# 12_USB_3.net
KiCad netlist of a schematic drawn in Altium Designer
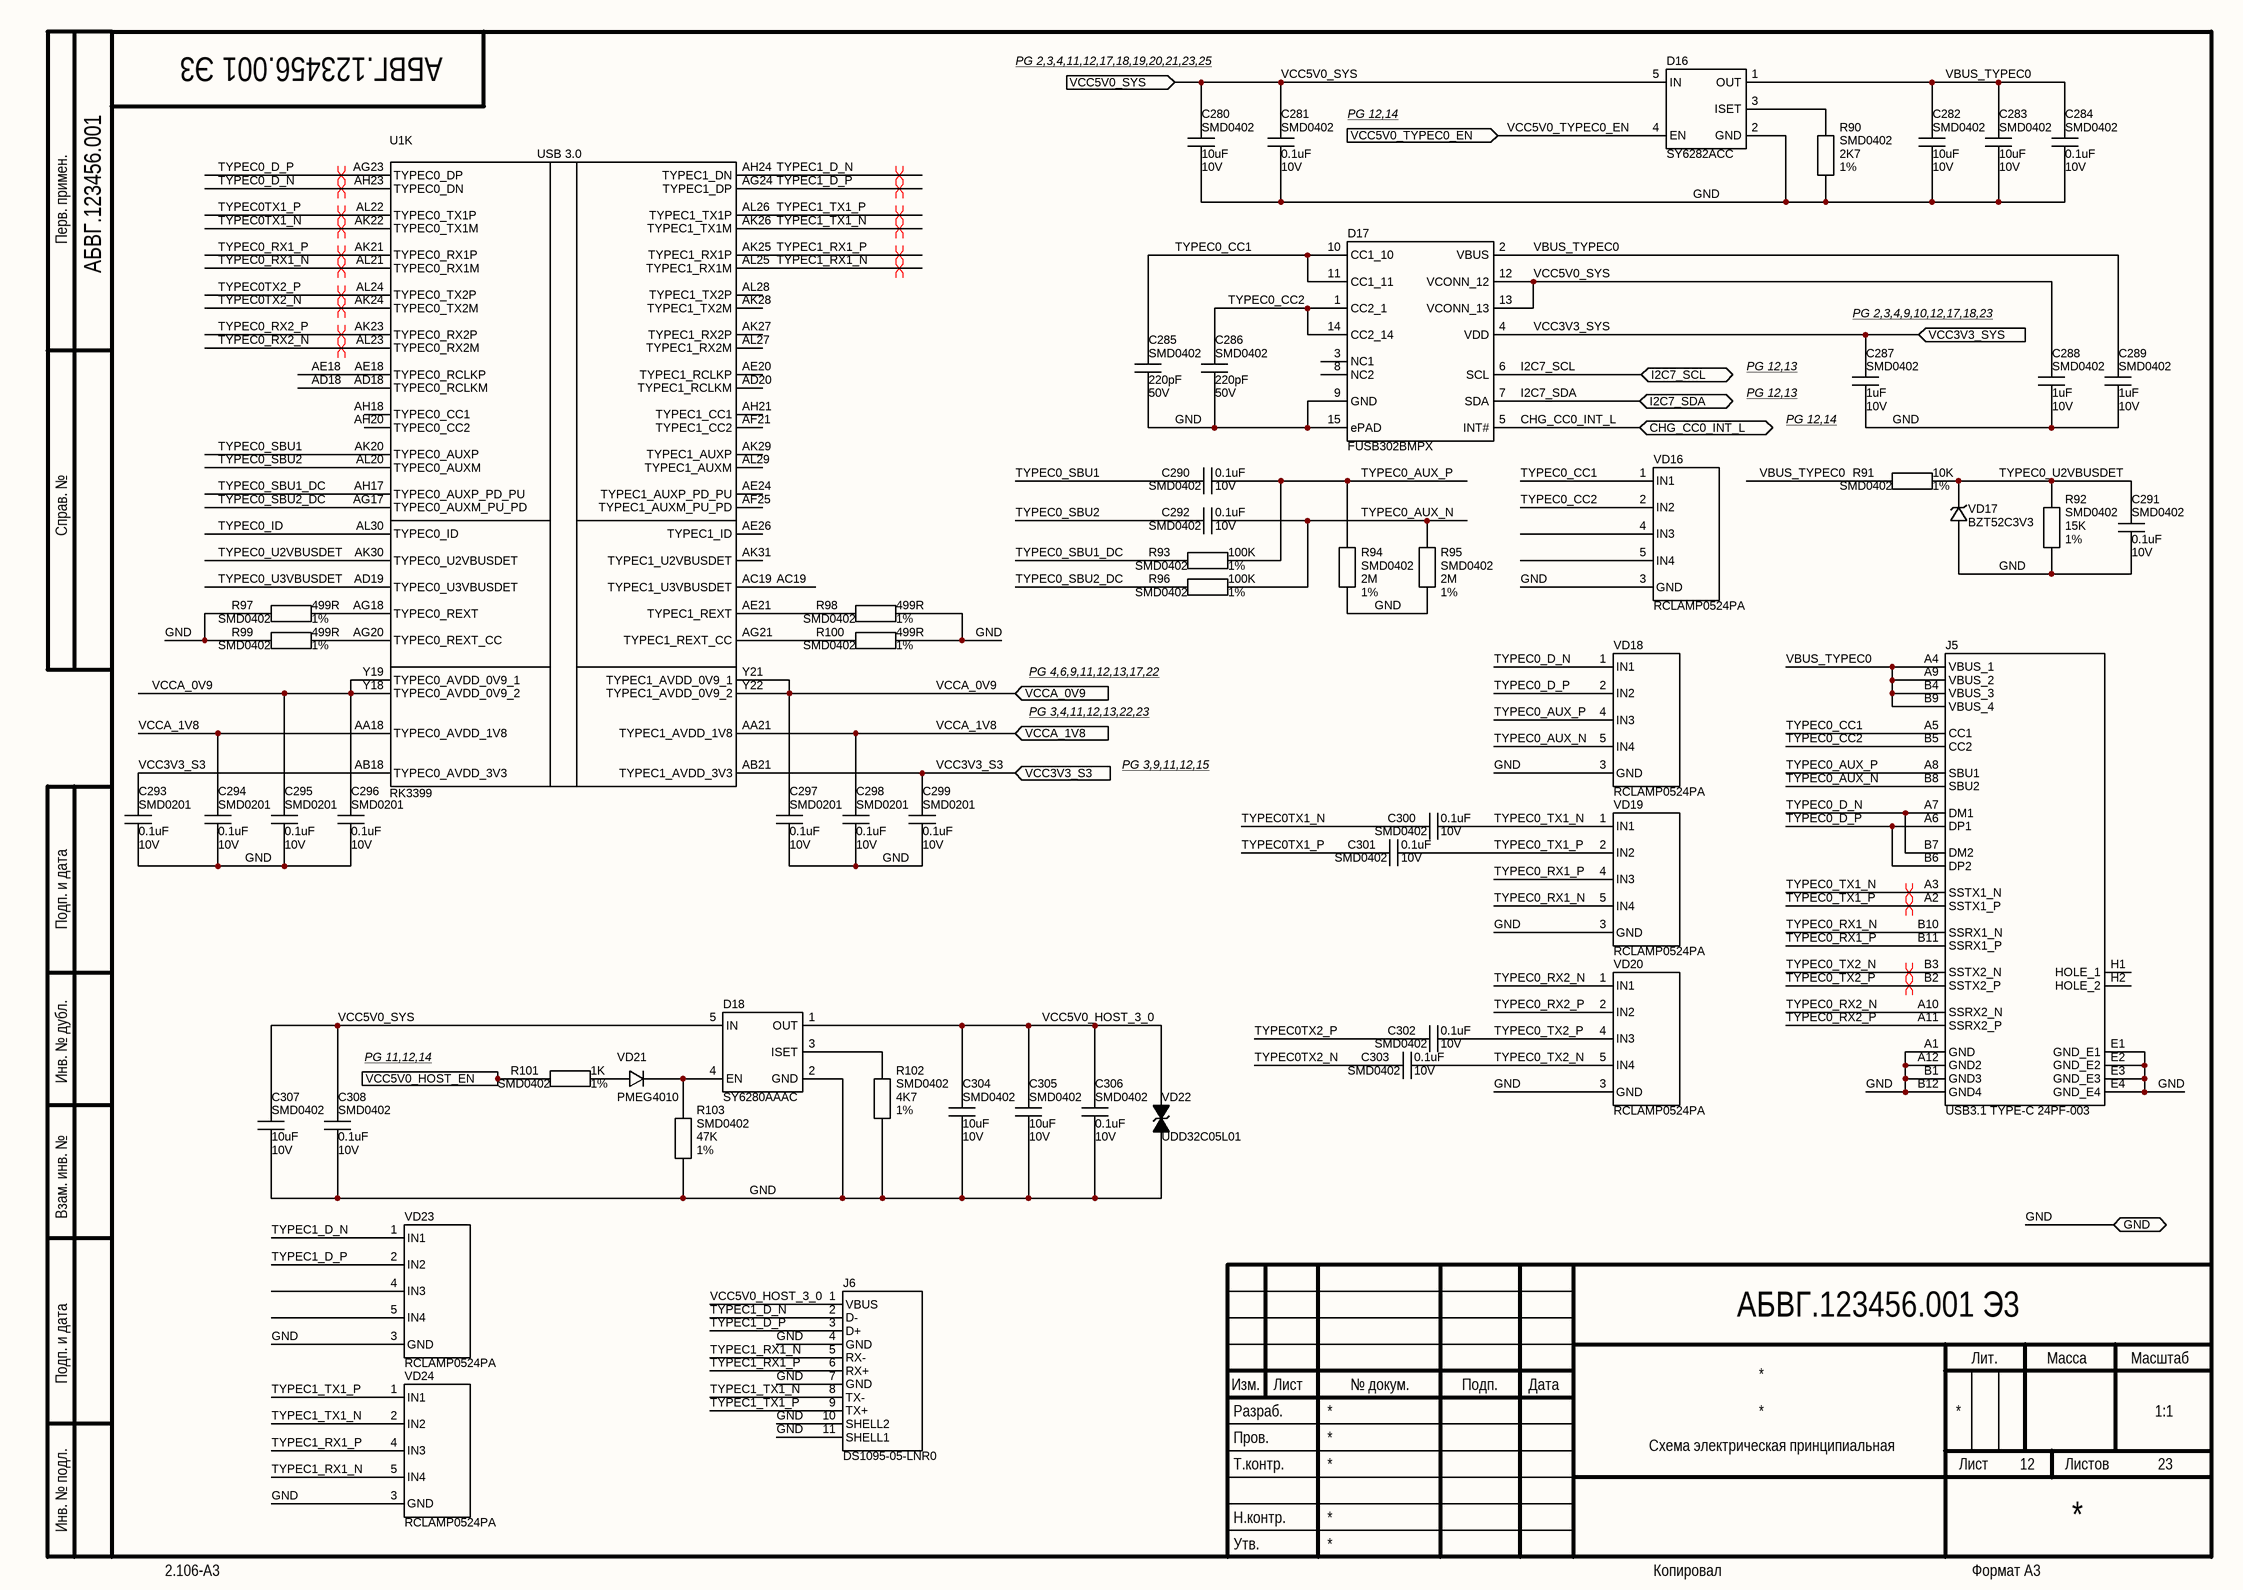
[diagram p0: 12 USB_3.SchDoc]

(export (version "E")
  (design (tool "Eeschema 10.0.6"))
  (components
    (comp (ref "C280")
      (value "10uF")
      (footprint "Didur_PcbLib_1:CAP_SMD_0402")
      (fields
        (field (name "PACKAGE") "SMD0402")
        (field (name "PARTNUMBER") "CC0402MRX5R6BB106")
        (field (name "VOLTAGE") "10V")
      )
      (libsource (lib "Didur_SchLib_1") (part "Ceramic_Cap"))
    )
    (comp (ref "C281")
      (value "0.1uF")
      (footprint "Didur_PcbLib_1:CAP_SMD_0402")
      (fields
        (field (name "PACKAGE") "SMD0402")
        (field (name "PARTNUMBER") "CC0402KRX5R6BB104")
        (field (name "VOLTAGE") "10V")
      )
      (libsource (lib "Didur_SchLib_1") (part "Ceramic_Cap"))
    )
    (comp (ref "C282")
      (value "10uF")
      (footprint "Didur_PcbLib_1:CAP_SMD_0402")
      (fields
        (field (name "PACKAGE") "SMD0402")
        (field (name "PARTNUMBER") "CC0402MRX5R6BB106")
        (field (name "VOLTAGE") "10V")
      )
      (libsource (lib "Didur_SchLib_1") (part "Ceramic_Cap"))
    )
    (comp (ref "C283")
      (value "10uF")
      (footprint "Didur_PcbLib_1:CAP_SMD_0402")
      (fields
        (field (name "PACKAGE") "SMD0402")
        (field (name "PARTNUMBER") "CC0402MRX5R6BB106")
        (field (name "VOLTAGE") "10V")
      )
      (libsource (lib "Didur_SchLib_1") (part "Ceramic_Cap"))
    )
    (comp (ref "C284")
      (value "0.1uF")
      (footprint "Didur_PcbLib_1:CAP_SMD_0402")
      (fields
        (field (name "PACKAGE") "SMD0402")
        (field (name "PARTNUMBER") "CC0402KRX5R6BB104")
        (field (name "VOLTAGE") "10V")
      )
      (libsource (lib "Didur_SchLib_1") (part "Ceramic_Cap"))
    )
    (comp (ref "C285")
      (value "220pF")
      (footprint "Didur_PcbLib_1:CAP_SMD_0402")
      (fields
        (field (name "PACKAGE") "SMD0402")
        (field (name "PARTNUMBER") "CC0402JRNPO9BN221")
        (field (name "VOLTAGE") "50V")
      )
      (libsource (lib "Didur_SchLib_1") (part "Ceramic_Cap"))
    )
    (comp (ref "C286")
      (value "220pF")
      (footprint "Didur_PcbLib_1:CAP_SMD_0402")
      (fields
        (field (name "PACKAGE") "SMD0402")
        (field (name "PARTNUMBER") "CC0402JRNPO9BN221")
        (field (name "VOLTAGE") "50V")
      )
      (libsource (lib "Didur_SchLib_1") (part "Ceramic_Cap"))
    )
    (comp (ref "C287")
      (value "1uF")
      (footprint "Didur_PcbLib_1:CAP_SMD_0402")
      (fields
        (field (name "PACKAGE") "SMD0402")
        (field (name "PARTNUMBER") "CC0402KRX5R6BB105")
        (field (name "VOLTAGE") "10V")
      )
      (libsource (lib "Didur_SchLib_1") (part "Ceramic_Cap"))
    )
    (comp (ref "C288")
      (value "1uF")
      (footprint "Didur_PcbLib_1:CAP_SMD_0402")
      (fields
        (field (name "PACKAGE") "SMD0402")
        (field (name "PARTNUMBER") "CC0402KRX5R6BB105")
        (field (name "VOLTAGE") "10V")
      )
      (libsource (lib "Didur_SchLib_1") (part "Ceramic_Cap"))
    )
    (comp (ref "C289")
      (value "1uF")
      (footprint "Didur_PcbLib_1:CAP_SMD_0402")
      (fields
        (field (name "PACKAGE") "SMD0402")
        (field (name "PARTNUMBER") "CC0402KRX5R6BB105")
        (field (name "VOLTAGE") "10V")
      )
      (libsource (lib "Didur_SchLib_1") (part "Ceramic_Cap"))
    )
    (comp (ref "C290")
      (value "0.1uF")
      (footprint "Didur_PcbLib_1:CAP_SMD_0402")
      (fields
        (field (name "PACKAGE") "SMD0402")
        (field (name "PARTNUMBER") "CC0402KRX5R6BB104")
        (field (name "VOLTAGE") "10V")
      )
      (libsource (lib "Didur_SchLib_1") (part "Ceramic_Cap"))
    )
    (comp (ref "C291")
      (value "0.1uF")
      (footprint "Didur_PcbLib_1:CAP_SMD_0402")
      (fields
        (field (name "PACKAGE") "SMD0402")
        (field (name "PARTNUMBER") "CC0402KRX5R6BB104")
        (field (name "VOLTAGE") "10V")
      )
      (libsource (lib "Didur_SchLib_1") (part "Ceramic_Cap"))
    )
    (comp (ref "C292")
      (value "0.1uF")
      (footprint "Didur_PcbLib_1:CAP_SMD_0402")
      (fields
        (field (name "PACKAGE") "SMD0402")
        (field (name "PARTNUMBER") "CC0402KRX5R6BB104")
        (field (name "VOLTAGE") "10V")
      )
      (libsource (lib "Didur_SchLib_1") (part "Ceramic_Cap"))
    )
    (comp (ref "C293")
      (value "0.1uF")
      (footprint "Didur_PcbLib_1:CAP_SMD_0201")
      (fields
        (field (name "PACKAGE") "SMD0201")
        (field (name "PARTNUMBER") "CC0201KRX5R6BB104")
        (field (name "VOLTAGE") "10V")
      )
      (libsource (lib "Didur_SchLib_1") (part "Ceramic_Cap"))
    )
    (comp (ref "C294")
      (value "0.1uF")
      (footprint "Didur_PcbLib_1:CAP_SMD_0201")
      (fields
        (field (name "PACKAGE") "SMD0201")
        (field (name "PARTNUMBER") "CC0201KRX5R6BB104")
        (field (name "VOLTAGE") "10V")
      )
      (libsource (lib "Didur_SchLib_1") (part "Ceramic_Cap"))
    )
    (comp (ref "C295")
      (value "0.1uF")
      (footprint "Didur_PcbLib_1:CAP_SMD_0201")
      (fields
        (field (name "PACKAGE") "SMD0201")
        (field (name "PARTNUMBER") "CC0201KRX5R6BB104")
        (field (name "VOLTAGE") "10V")
      )
      (libsource (lib "Didur_SchLib_1") (part "Ceramic_Cap"))
    )
    (comp (ref "C296")
      (value "0.1uF")
      (footprint "Didur_PcbLib_1:CAP_SMD_0201")
      (fields
        (field (name "PACKAGE") "SMD0201")
        (field (name "PARTNUMBER") "CC0201KRX5R6BB104")
        (field (name "VOLTAGE") "10V")
      )
      (libsource (lib "Didur_SchLib_1") (part "Ceramic_Cap"))
    )
    (comp (ref "C297")
      (value "0.1uF")
      (footprint "Didur_PcbLib_1:CAP_SMD_0201")
      (fields
        (field (name "PACKAGE") "SMD0201")
        (field (name "PARTNUMBER") "CC0201KRX5R6BB104")
        (field (name "VOLTAGE") "10V")
      )
      (libsource (lib "Didur_SchLib_1") (part "Ceramic_Cap"))
    )
    (comp (ref "C298")
      (value "0.1uF")
      (footprint "Didur_PcbLib_1:CAP_SMD_0201")
      (fields
        (field (name "PACKAGE") "SMD0201")
        (field (name "PARTNUMBER") "CC0201KRX5R6BB104")
        (field (name "VOLTAGE") "10V")
      )
      (libsource (lib "Didur_SchLib_1") (part "Ceramic_Cap"))
    )
    (comp (ref "C299")
      (value "0.1uF")
      (footprint "Didur_PcbLib_1:CAP_SMD_0201")
      (fields
        (field (name "PACKAGE") "SMD0201")
        (field (name "PARTNUMBER") "CC0201KRX5R6BB104")
        (field (name "VOLTAGE") "10V")
      )
      (libsource (lib "Didur_SchLib_1") (part "Ceramic_Cap"))
    )
    (comp (ref "C300")
      (value "0.1uF")
      (footprint "Didur_PcbLib_1:CAP_SMD_0402")
      (fields
        (field (name "PACKAGE") "SMD0402")
        (field (name "PARTNUMBER") "CC0402KRX5R6BB104")
        (field (name "VOLTAGE") "10V")
      )
      (libsource (lib "Didur_SchLib_1") (part "Ceramic_Cap"))
    )
    (comp (ref "C301")
      (value "0.1uF")
      (footprint "Didur_PcbLib_1:CAP_SMD_0402")
      (fields
        (field (name "PACKAGE") "SMD0402")
        (field (name "PARTNUMBER") "CC0402KRX5R6BB104")
        (field (name "VOLTAGE") "10V")
      )
      (libsource (lib "Didur_SchLib_1") (part "Ceramic_Cap"))
    )
    (comp (ref "C302")
      (value "0.1uF")
      (footprint "Didur_PcbLib_1:CAP_SMD_0402")
      (fields
        (field (name "PACKAGE") "SMD0402")
        (field (name "PARTNUMBER") "CC0402KRX5R6BB104")
        (field (name "VOLTAGE") "10V")
      )
      (libsource (lib "Didur_SchLib_1") (part "Ceramic_Cap"))
    )
    (comp (ref "C303")
      (value "0.1uF")
      (footprint "Didur_PcbLib_1:CAP_SMD_0402")
      (fields
        (field (name "PACKAGE") "SMD0402")
        (field (name "PARTNUMBER") "CC0402KRX5R6BB104")
        (field (name "VOLTAGE") "10V")
      )
      (libsource (lib "Didur_SchLib_1") (part "Ceramic_Cap"))
    )
    (comp (ref "C304")
      (value "10uF")
      (footprint "Didur_PcbLib_1:CAP_SMD_0402")
      (fields
        (field (name "PACKAGE") "SMD0402")
        (field (name "PARTNUMBER") "CC0402MRX5R6BB106")
        (field (name "VOLTAGE") "10V")
      )
      (libsource (lib "Didur_SchLib_1") (part "Ceramic_Cap"))
    )
    (comp (ref "C305")
      (value "10uF")
      (footprint "Didur_PcbLib_1:CAP_SMD_0402")
      (fields
        (field (name "PACKAGE") "SMD0402")
        (field (name "PARTNUMBER") "CC0402MRX5R6BB106")
        (field (name "VOLTAGE") "10V")
      )
      (libsource (lib "Didur_SchLib_1") (part "Ceramic_Cap"))
    )
    (comp (ref "C306")
      (value "0.1uF")
      (footprint "Didur_PcbLib_1:CAP_SMD_0402")
      (fields
        (field (name "PACKAGE") "SMD0402")
        (field (name "PARTNUMBER") "CC0402KRX5R6BB104")
        (field (name "VOLTAGE") "10V")
      )
      (libsource (lib "Didur_SchLib_1") (part "Ceramic_Cap"))
    )
    (comp (ref "C307")
      (value "10uF")
      (footprint "Didur_PcbLib_1:CAP_SMD_0402")
      (fields
        (field (name "PACKAGE") "SMD0402")
        (field (name "PARTNUMBER") "CC0402MRX5R6BB106")
        (field (name "VOLTAGE") "10V")
      )
      (libsource (lib "Didur_SchLib_1") (part "Ceramic_Cap"))
    )
    (comp (ref "C308")
      (value "0.1uF")
      (footprint "Didur_PcbLib_1:CAP_SMD_0402")
      (fields
        (field (name "PACKAGE") "SMD0402")
        (field (name "PARTNUMBER") "CC0402KRX5R6BB104")
        (field (name "VOLTAGE") "10V")
      )
      (libsource (lib "Didur_SchLib_1") (part "Ceramic_Cap"))
    )
    (comp (ref "D16")
      (value "SY6282ACC")
      (footprint "Didur_PcbLib_1:SOT23-5")
      (libsource (lib "Didur_SchLib_1") (part "SY6280AAAC"))
    )
    (comp (ref "D17")
      (value "FUSB302BMPX")
      (footprint "Didur_PcbLib_1:WQFN14")
      (libsource (lib "Didur_SchLib_1") (part "FUSB302BMPX"))
    )
    (comp (ref "D18")
      (value "SY6280AAAC")
      (footprint "Didur_PcbLib_1:SOT23-5")
      (libsource (lib "Didur_SchLib_1") (part "SY6280AAAC"))
    )
    (comp (ref "J5")
      (value "USB3.1 TYPE-C 24PF-003")
      (footprint "Didur_PcbLib_1:USB3.1 TYPE-C 24PF-003")
      (libsource (lib "Didur_SchLib_1") (part "TYPEC_FUCR-248X-10XX"))
    )
    (comp (ref "J6")
      (value "DS1095-05-LNR0")
      (footprint "Didur_PcbLib_1:DS1095-05-LNR0")
      (libsource (lib "Didur_SchLib_1") (part "USB3D0_AF_9P"))
    )
    (comp (ref "R90")
      (value "2K7")
      (footprint "Didur_PcbLib_1:RES_SMD_0402")
      (fields
        (field (name "PACKAGE") "SMD0402")
        (field (name "PARTNUMBER") "RC0402FR-072K7L")
        (field (name "TOLERANCE") "1%")
      )
      (libsource (lib "Didur_SchLib_1") (part "Chip_Res"))
    )
    (comp (ref "R91")
      (value "10K")
      (footprint "Didur_PcbLib_1:RES_SMD_0402")
      (fields
        (field (name "PACKAGE") "SMD0402")
        (field (name "PARTNUMBER") "RC0402FR-0710KL")
        (field (name "TOLERANCE") "1%")
      )
      (libsource (lib "Didur_SchLib_1") (part "Chip_Res"))
    )
    (comp (ref "R92")
      (value "15K")
      (footprint "Didur_PcbLib_1:RES_SMD_0402")
      (fields
        (field (name "PACKAGE") "SMD0402")
        (field (name "PARTNUMBER") "RC0402FR-0715KL")
        (field (name "TOLERANCE") "1%")
      )
      (libsource (lib "Didur_SchLib_1") (part "Chip_Res"))
    )
    (comp (ref "R93")
      (value "100K")
      (footprint "Didur_PcbLib_1:RES_SMD_0402")
      (fields
        (field (name "PACKAGE") "SMD0402")
        (field (name "PARTNUMBER") "RC0402FR-07100KL")
        (field (name "TOLERANCE") "1%")
      )
      (libsource (lib "") (part "Chip_Res_1"))
    )
    (comp (ref "R94")
      (value "2M")
      (footprint "Didur_PcbLib_1:RES_SMD_0402")
      (fields
        (field (name "PACKAGE") "SMD0402")
        (field (name "PARTNUMBER") "RC0402FR-072ML")
        (field (name "TOLERANCE") "1%")
      )
      (libsource (lib "") (part "Chip_Res_2"))
    )
    (comp (ref "R95")
      (value "2M")
      (footprint "Didur_PcbLib_1:RES_SMD_0402")
      (fields
        (field (name "PACKAGE") "SMD0402")
        (field (name "PARTNUMBER") "RC0402FR-072ML")
        (field (name "TOLERANCE") "1%")
      )
      (libsource (lib "") (part "Chip_Res_2"))
    )
    (comp (ref "R96")
      (value "100K")
      (footprint "Didur_PcbLib_1:RES_SMD_0402")
      (fields
        (field (name "PACKAGE") "SMD0402")
        (field (name "PARTNUMBER") "RC0402FR-07100KL")
        (field (name "TOLERANCE") "1%")
      )
      (libsource (lib "") (part "Chip_Res_1"))
    )
    (comp (ref "R97")
      (value "499R")
      (footprint "Didur_PcbLib_1:RES_SMD_0402_SMALL")
      (fields
        (field (name "PACKAGE") "SMD0402")
        (field (name "PARTNUMBER") "RC0402FR-07499RL")
        (field (name "TOLERANCE") "1%")
      )
      (libsource (lib "") (part "Chip_Res_1"))
    )
    (comp (ref "R98")
      (value "499R")
      (footprint "Didur_PcbLib_1:RES_SMD_0402_SMALL")
      (fields
        (field (name "PACKAGE") "SMD0402")
        (field (name "PARTNUMBER") "RC0402FR-07499RL")
        (field (name "TOLERANCE") "1%")
      )
      (libsource (lib "") (part "Chip_Res_1"))
    )
    (comp (ref "R99")
      (value "499R")
      (footprint "Didur_PcbLib_1:RES_SMD_0402_SMALL")
      (fields
        (field (name "PACKAGE") "SMD0402")
        (field (name "PARTNUMBER") "RC0402FR-07499RL")
        (field (name "TOLERANCE") "1%")
      )
      (libsource (lib "") (part "Chip_Res_1"))
    )
    (comp (ref "R100")
      (value "499R")
      (footprint "Didur_PcbLib_1:RES_SMD_0402_SMALL")
      (fields
        (field (name "PACKAGE") "SMD0402")
        (field (name "PARTNUMBER") "RC0402FR-07499RL")
        (field (name "TOLERANCE") "1%")
      )
      (libsource (lib "") (part "Chip_Res_1"))
    )
    (comp (ref "R101")
      (value "1K")
      (footprint "Didur_PcbLib_1:RES_SMD_0402")
      (fields
        (field (name "PACKAGE") "SMD0402")
        (field (name "PARTNUMBER") "RC0402FR-071KL")
        (field (name "TOLERANCE") "1%")
      )
      (libsource (lib "") (part "Chip_Res_3"))
    )
    (comp (ref "R102")
      (value "4K7")
      (footprint "Didur_PcbLib_1:RES_SMD_0402")
      (fields
        (field (name "PACKAGE") "SMD0402")
        (field (name "PARTNUMBER") "RC0402FR-074K7L")
        (field (name "TOLERANCE") "1%")
      )
      (libsource (lib "Didur_SchLib_1") (part "Chip_Res"))
    )
    (comp (ref "R103")
      (value "47K")
      (footprint "Didur_PcbLib_1:RES_SMD_0402")
      (fields
        (field (name "PACKAGE") "SMD0402")
        (field (name "PARTNUMBER") "RC0402FR-1347KL")
        (field (name "TOLERANCE") "1%")
      )
      (libsource (lib "Didur_SchLib_1") (part "Chip_Res"))
    )
    (comp (ref "U1")
      (value "RK3399")
      (footprint "BGA828C65P31X31_2100X2100X161N")
      (fields (field (name "Comment") "RK3399_FF"))
      (libsource (lib "Didur_SchLib_1") (part "RK3399_FF"))
    )
    (comp (ref "VD16")
      (value "RCLAMP0524PA")
      (footprint "Didur_PcbLib_1:RCLAMP0524PA")
      (libsource (lib "Didur_SchLib_1") (part "RCLAMP0524PA"))
    )
    (comp (ref "VD17")
      (value "BZT52C3V3")
      (footprint "SOD323")
      (libsource (lib "Didur_SchLib_1") (part "ZenerDiode"))
    )
    (comp (ref "VD18")
      (value "RCLAMP0524PA")
      (footprint "Didur_PcbLib_1:RCLAMP0524PA")
      (libsource (lib "Didur_SchLib_1") (part "RCLAMP0524PA"))
    )
    (comp (ref "VD19")
      (value "RCLAMP0524PA")
      (footprint "Didur_PcbLib_1:RCLAMP0524PA")
      (libsource (lib "Didur_SchLib_1") (part "RCLAMP0524PA"))
    )
    (comp (ref "VD20")
      (value "RCLAMP0524PA")
      (footprint "Didur_PcbLib_1:RCLAMP0524PA")
      (libsource (lib "Didur_SchLib_1") (part "RCLAMP0524PA"))
    )
    (comp (ref "VD21")
      (value "PMEG4010")
      (footprint "SOD323")
      (fields (field (name "PARTNUMBER") "PMEG4010CEJ.115") (field (name "Comment") "Diode"))
      (libsource (lib "Didur_SchLib_1") (part "Diode"))
    )
    (comp (ref "VD22")
      (value "UDD32C05L01")
      (footprint "Didur_PcbLib_1:SOD323")
      (fields (field (name "Comment") "TVS_Diode"))
      (libsource (lib "Didur_SchLib_1") (part "TVS_Diode"))
    )
    (comp (ref "VD23")
      (value "RCLAMP0524PA")
      (footprint "Didur_PcbLib_1:RCLAMP0524PA")
      (libsource (lib "Didur_SchLib_1") (part "RCLAMP0524PA"))
    )
    (comp (ref "VD24")
      (value "RCLAMP0524PA")
      (footprint "Didur_PcbLib_1:RCLAMP0524PA")
      (libsource (lib "Didur_SchLib_1") (part "RCLAMP0524PA"))
    )
  )
  (nets
    (net (code "1") (name "/AC19") (class "Default")
      (node (ref "U1") (pin "AC19") (pinfunction "TYPEC1_U3VBUSDET_AC19") (pintype "passive"))
    )
    (net (code "2") (name "/AD18") (class "Default")
      (node (ref "U1") (pin "AD18") (pinfunction "TYPEC0_RCLKM_AD18") (pintype "passive"))
    )
    (net (code "3") (name "/AE18") (class "Default")
      (node (ref "U1") (pin "AE18") (pinfunction "TYPEC0_RCLKP_AE18") (pintype "passive"))
    )
    (net (code "4") (name "/CHG_CC0_INT_L") (class "Default")
      (node (ref "D17") (pin "5") (pinfunction "INT#_5") (pintype "passive"))
    )
    (net (code "5") (name "/GND") (class "Default")
      (node (ref "C280") (pin "2") (pinfunction "2_2") (pintype "power_in"))
      (node (ref "C281") (pin "2") (pinfunction "2_2") (pintype "power_in"))
      (node (ref "C282") (pin "2") (pinfunction "2_2") (pintype "power_in"))
      (node (ref "C283") (pin "2") (pinfunction "2_2") (pintype "power_in"))
      (node (ref "C284") (pin "2") (pinfunction "2_2") (pintype "power_in"))
      (node (ref "C285") (pin "2") (pinfunction "2_2") (pintype "power_in"))
      (node (ref "C286") (pin "2") (pinfunction "2_2") (pintype "power_in"))
      (node (ref "C287") (pin "2") (pinfunction "2_2") (pintype "power_in"))
      (node (ref "C288") (pin "2") (pinfunction "2_2") (pintype "power_in"))
      (node (ref "C289") (pin "2") (pinfunction "2_2") (pintype "power_in"))
      (node (ref "C291") (pin "2") (pinfunction "2_2") (pintype "power_in"))
      (node (ref "C293") (pin "2") (pinfunction "2_2") (pintype "power_in"))
      (node (ref "C294") (pin "2") (pinfunction "2_2") (pintype "power_in"))
      (node (ref "C295") (pin "2") (pinfunction "2_2") (pintype "power_in"))
      (node (ref "C296") (pin "2") (pinfunction "2_2") (pintype "power_in"))
      (node (ref "C297") (pin "2") (pinfunction "2_2") (pintype "power_in"))
      (node (ref "C298") (pin "2") (pinfunction "2_2") (pintype "power_in"))
      (node (ref "C299") (pin "2") (pinfunction "2_2") (pintype "power_in"))
      (node (ref "C304") (pin "2") (pinfunction "2_2") (pintype "power_in"))
      (node (ref "C305") (pin "2") (pinfunction "2_2") (pintype "power_in"))
      (node (ref "C306") (pin "2") (pinfunction "2_2") (pintype "power_in"))
      (node (ref "C307") (pin "2") (pinfunction "2_2") (pintype "power_in"))
      (node (ref "C308") (pin "2") (pinfunction "2_2") (pintype "power_in"))
      (node (ref "D16") (pin "2") (pinfunction "GND_2") (pintype "passive"))
      (node (ref "D17") (pin "15") (pinfunction "ePAD_15") (pintype "passive"))
      (node (ref "D17") (pin "9") (pinfunction "GND_9") (pintype "passive"))
      (node (ref "D18") (pin "2") (pinfunction "GND_2") (pintype "passive"))
      (node (ref "J5") (pin "A1") (pinfunction "GND_A1") (pintype "passive"))
      (node (ref "J5") (pin "A12") (pinfunction "GND2_A12") (pintype "passive"))
      (node (ref "J5") (pin "B1") (pinfunction "GND3_B1") (pintype "passive"))
      (node (ref "J5") (pin "B12") (pinfunction "GND4_B12") (pintype "passive"))
      (node (ref "J5") (pin "E1") (pinfunction "GND_E1_E1") (pintype "passive"))
      (node (ref "J5") (pin "E2") (pinfunction "GND_E2_E2") (pintype "passive"))
      (node (ref "J5") (pin "E3") (pinfunction "GND_E3_E3") (pintype "passive"))
      (node (ref "J5") (pin "E4") (pinfunction "GND_E4_E4") (pintype "passive"))
      (node (ref "J6") (pin "10") (pinfunction "SHELL2_10") (pintype "passive"))
      (node (ref "J6") (pin "11") (pinfunction "SHELL1_11") (pintype "passive"))
      (node (ref "J6") (pin "4") (pinfunction "GND_4") (pintype "passive"))
      (node (ref "J6") (pin "7") (pinfunction "GND_7") (pintype "passive"))
      (node (ref "R100") (pin "1") (pinfunction "1_1") (pintype "passive"))
      (node (ref "R102") (pin "2") (pinfunction "2_2") (pintype "passive"))
      (node (ref "R103") (pin "2") (pinfunction "2_2") (pintype "passive"))
      (node (ref "R90") (pin "2") (pinfunction "2_2") (pintype "passive"))
      (node (ref "R92") (pin "2") (pinfunction "2_2") (pintype "passive"))
      (node (ref "R94") (pin "1") (pinfunction "1_1") (pintype "passive"))
      (node (ref "R95") (pin "1") (pinfunction "1_1") (pintype "passive"))
      (node (ref "R97") (pin "2") (pinfunction "2_2") (pintype "passive"))
      (node (ref "R98") (pin "1") (pinfunction "1_1") (pintype "passive"))
      (node (ref "R99") (pin "2") (pinfunction "2_2") (pintype "passive"))
      (node (ref "VD16") (pin "3") (pinfunction "GND_3") (pintype "passive"))
      (node (ref "VD17") (pin "1") (pinfunction "A_1") (pintype "passive"))
      (node (ref "VD18") (pin "3") (pinfunction "GND_3") (pintype "passive"))
      (node (ref "VD19") (pin "3") (pinfunction "GND_3") (pintype "passive"))
      (node (ref "VD20") (pin "3") (pinfunction "GND_3") (pintype "passive"))
      (node (ref "VD22") (pin "1") (pinfunction "A_1") (pintype "passive"))
      (node (ref "VD23") (pin "3") (pinfunction "GND_3") (pintype "passive"))
      (node (ref "VD24") (pin "3") (pinfunction "GND_3") (pintype "passive"))
    )
    (net (code "6") (name "/I2C7_SCL") (class "Default")
      (node (ref "D17") (pin "6") (pinfunction "SCL_6") (pintype "passive"))
    )
    (net (code "7") (name "/I2C7_SDA") (class "Default")
      (node (ref "D17") (pin "7") (pinfunction "SDA_7") (pintype "passive"))
    )
    (net (code "8") (name "/TYPEC0TX1_N") (class "Default")
      (node (ref "C300") (pin "1") (pinfunction "1_1") (pintype "power_in"))
      (node (ref "U1") (pin "AK22") (pinfunction "TYPEC0_TX1M_AK22") (pintype "passive"))
    )
    (net (code "9") (name "/TYPEC0TX1_P") (class "Default")
      (node (ref "C301") (pin "1") (pinfunction "1_1") (pintype "power_in"))
      (node (ref "U1") (pin "AL22") (pinfunction "TYPEC0_TX1P_AL22") (pintype "passive"))
    )
    (net (code "10") (name "/TYPEC0TX2_N") (class "Default")
      (node (ref "C303") (pin "1") (pinfunction "1_1") (pintype "power_in"))
      (node (ref "U1") (pin "AK24") (pinfunction "TYPEC0_TX2M_AK24") (pintype "passive"))
    )
    (net (code "11") (name "/TYPEC0TX2_P") (class "Default")
      (node (ref "C302") (pin "1") (pinfunction "1_1") (pintype "power_in"))
      (node (ref "U1") (pin "AL24") (pinfunction "TYPEC0_TX2P_AL24") (pintype "passive"))
    )
    (net (code "12") (name "/TYPEC0_AUX_N") (class "Default")
      (node (ref "C292") (pin "2") (pinfunction "2_2") (pintype "power_in"))
      (node (ref "J5") (pin "B8") (pinfunction "SBU2_B8") (pintype "passive"))
      (node (ref "R95") (pin "2") (pinfunction "2_2") (pintype "passive"))
      (node (ref "R96") (pin "1") (pinfunction "1_1") (pintype "passive"))
      (node (ref "VD18") (pin "5") (pinfunction "IN4_5") (pintype "passive"))
    )
    (net (code "13") (name "/TYPEC0_AUX_P") (class "Default")
      (node (ref "C290") (pin "2") (pinfunction "2_2") (pintype "power_in"))
      (node (ref "J5") (pin "A8") (pinfunction "SBU1_A8") (pintype "passive"))
      (node (ref "R93") (pin "1") (pinfunction "1_1") (pintype "passive"))
      (node (ref "R94") (pin "2") (pinfunction "2_2") (pintype "passive"))
      (node (ref "VD18") (pin "4") (pinfunction "IN3_4") (pintype "passive"))
    )
    (net (code "14") (name "/TYPEC0_CC1") (class "Default")
      (node (ref "C285") (pin "1") (pinfunction "1_1") (pintype "power_in"))
      (node (ref "D17") (pin "10") (pinfunction "CC1_10_10") (pintype "passive"))
      (node (ref "D17") (pin "11") (pinfunction "CC1_11_11") (pintype "passive"))
      (node (ref "J5") (pin "A5") (pinfunction "CC1_A5") (pintype "passive"))
      (node (ref "VD16") (pin "1") (pinfunction "IN1_1") (pintype "passive"))
    )
    (net (code "15") (name "/TYPEC0_CC2") (class "Default")
      (node (ref "C286") (pin "1") (pinfunction "1_1") (pintype "power_in"))
      (node (ref "D17") (pin "1") (pinfunction "CC2_1_1") (pintype "passive"))
      (node (ref "D17") (pin "14") (pinfunction "CC2_14_14") (pintype "passive"))
      (node (ref "J5") (pin "B5") (pinfunction "CC2_B5") (pintype "passive"))
      (node (ref "VD16") (pin "2") (pinfunction "IN2_2") (pintype "passive"))
    )
    (net (code "16") (name "/TYPEC0_D_N") (class "Default")
      (node (ref "J5") (pin "A7") (pinfunction "DM1_A7") (pintype "passive"))
      (node (ref "J5") (pin "B7") (pinfunction "DM2_B7") (pintype "passive"))
      (node (ref "U1") (pin "AH23") (pinfunction "TYPEC0_DN_AH23") (pintype "passive"))
      (node (ref "VD18") (pin "1") (pinfunction "IN1_1") (pintype "passive"))
    )
    (net (code "17") (name "/TYPEC0_D_P") (class "Default")
      (node (ref "J5") (pin "A6") (pinfunction "DP1_A6") (pintype "passive"))
      (node (ref "J5") (pin "B6") (pinfunction "DP2_B6") (pintype "passive"))
      (node (ref "U1") (pin "AG23") (pinfunction "TYPEC0_DP_AG23") (pintype "passive"))
      (node (ref "VD18") (pin "2") (pinfunction "IN2_2") (pintype "passive"))
    )
    (net (code "18") (name "/TYPEC0_ID") (class "Default")
      (node (ref "U1") (pin "AL30") (pinfunction "TYPEC0_ID_AL30") (pintype "passive"))
    )
    (net (code "19") (name "/TYPEC0_RX1_N") (class "Default")
      (node (ref "J5") (pin "B10") (pinfunction "SSRX1_N_B10") (pintype "passive"))
      (node (ref "U1") (pin "AL21") (pinfunction "TYPEC0_RX1M_AL21") (pintype "passive"))
      (node (ref "VD19") (pin "5") (pinfunction "IN4_5") (pintype "passive"))
    )
    (net (code "20") (name "/TYPEC0_RX1_P") (class "Default")
      (node (ref "J5") (pin "B11") (pinfunction "SSRX1_P_B11") (pintype "passive"))
      (node (ref "U1") (pin "AK21") (pinfunction "TYPEC0_RX1P_AK21") (pintype "passive"))
      (node (ref "VD19") (pin "4") (pinfunction "IN3_4") (pintype "passive"))
    )
    (net (code "21") (name "/TYPEC0_RX2_N") (class "Default")
      (node (ref "J5") (pin "A10") (pinfunction "SSRX2_N_A10") (pintype "passive"))
      (node (ref "U1") (pin "AL23") (pinfunction "TYPEC0_RX2M_AL23") (pintype "passive"))
      (node (ref "VD20") (pin "1") (pinfunction "IN1_1") (pintype "passive"))
    )
    (net (code "22") (name "/TYPEC0_RX2_P") (class "Default")
      (node (ref "J5") (pin "A11") (pinfunction "SSRX2_P_A11") (pintype "passive"))
      (node (ref "U1") (pin "AK23") (pinfunction "TYPEC0_RX2P_AK23") (pintype "passive"))
      (node (ref "VD20") (pin "2") (pinfunction "IN2_2") (pintype "passive"))
    )
    (net (code "23") (name "/TYPEC0_SBU1") (class "Default")
      (node (ref "C290") (pin "1") (pinfunction "1_1") (pintype "power_in"))
      (node (ref "U1") (pin "AK20") (pinfunction "TYPEC0_AUXP_AK20") (pintype "passive"))
    )
    (net (code "24") (name "/TYPEC0_SBU1_DC") (class "Default")
      (node (ref "R93") (pin "2") (pinfunction "2_2") (pintype "passive"))
      (node (ref "U1") (pin "AH17") (pinfunction "TYPEC0_AUXP_PD_PU_AH17") (pintype "passive"))
    )
    (net (code "25") (name "/TYPEC0_SBU2") (class "Default")
      (node (ref "C292") (pin "1") (pinfunction "1_1") (pintype "power_in"))
      (node (ref "U1") (pin "AL20") (pinfunction "TYPEC0_AUXM_AL20") (pintype "passive"))
    )
    (net (code "26") (name "/TYPEC0_SBU2_DC") (class "Default")
      (node (ref "R96") (pin "2") (pinfunction "2_2") (pintype "passive"))
      (node (ref "U1") (pin "AG17") (pinfunction "TYPEC0_AUXM_PU_PD_AG17") (pintype "passive"))
    )
    (net (code "27") (name "/TYPEC0_TX1_N") (class "Default")
      (node (ref "C300") (pin "2") (pinfunction "2_2") (pintype "power_in"))
      (node (ref "J5") (pin "A3") (pinfunction "SSTX1_N_A3") (pintype "passive"))
      (node (ref "VD19") (pin "1") (pinfunction "IN1_1") (pintype "passive"))
    )
    (net (code "28") (name "/TYPEC0_TX1_P") (class "Default")
      (node (ref "C301") (pin "2") (pinfunction "2_2") (pintype "power_in"))
      (node (ref "J5") (pin "A2") (pinfunction "SSTX1_P_A2") (pintype "passive"))
      (node (ref "VD19") (pin "2") (pinfunction "IN2_2") (pintype "passive"))
    )
    (net (code "29") (name "/TYPEC0_TX2_N") (class "Default")
      (node (ref "C303") (pin "2") (pinfunction "2_2") (pintype "power_in"))
      (node (ref "J5") (pin "B3") (pinfunction "SSTX2_N_B3") (pintype "passive"))
      (node (ref "VD20") (pin "5") (pinfunction "IN4_5") (pintype "passive"))
    )
    (net (code "30") (name "/TYPEC0_TX2_P") (class "Default")
      (node (ref "C302") (pin "2") (pinfunction "2_2") (pintype "power_in"))
      (node (ref "J5") (pin "B2") (pinfunction "SSTX2_P_B2") (pintype "passive"))
      (node (ref "VD20") (pin "4") (pinfunction "IN3_4") (pintype "passive"))
    )
    (net (code "31") (name "/TYPEC0_U2VBUSDET") (class "Default")
      (node (ref "C291") (pin "1") (pinfunction "1_1") (pintype "power_in"))
      (node (ref "R91") (pin "1") (pinfunction "1_1") (pintype "passive"))
      (node (ref "R92") (pin "1") (pinfunction "1_1") (pintype "passive"))
      (node (ref "U1") (pin "AK30") (pinfunction "TYPEC0_U2VBUSDET_AK30") (pintype "passive"))
      (node (ref "VD17") (pin "2") (pinfunction "C_2") (pintype "passive"))
    )
    (net (code "32") (name "/TYPEC0_U3VBUSDET") (class "Default")
      (node (ref "U1") (pin "AD19") (pinfunction "TYPEC0_U3VBUSDET_AD19") (pintype "passive"))
    )
    (net (code "33") (name "/TYPEC1_D_N") (class "Default")
      (node (ref "J6") (pin "2") (pinfunction "D-_2") (pintype "passive"))
      (node (ref "U1") (pin "AH24") (pinfunction "TYPEC1_DN_AH24") (pintype "passive"))
      (node (ref "VD23") (pin "1") (pinfunction "IN1_1") (pintype "passive"))
    )
    (net (code "34") (name "/TYPEC1_D_P") (class "Default")
      (node (ref "J6") (pin "3") (pinfunction "D+_3") (pintype "passive"))
      (node (ref "U1") (pin "AG24") (pinfunction "TYPEC1_DP_AG24") (pintype "passive"))
      (node (ref "VD23") (pin "2") (pinfunction "IN2_2") (pintype "passive"))
    )
    (net (code "35") (name "/TYPEC1_RX1_N") (class "Default")
      (node (ref "J6") (pin "5") (pinfunction "RX-_5") (pintype "passive"))
      (node (ref "U1") (pin "AL25") (pinfunction "TYPEC1_RX1M_AL25") (pintype "passive"))
      (node (ref "VD24") (pin "5") (pinfunction "IN4_5") (pintype "passive"))
    )
    (net (code "36") (name "/TYPEC1_RX1_P") (class "Default")
      (node (ref "J6") (pin "6") (pinfunction "RX+_6") (pintype "passive"))
      (node (ref "U1") (pin "AK25") (pinfunction "TYPEC1_RX1P_AK25") (pintype "passive"))
      (node (ref "VD24") (pin "4") (pinfunction "IN3_4") (pintype "passive"))
    )
    (net (code "37") (name "/TYPEC1_TX1_N") (class "Default")
      (node (ref "J6") (pin "8") (pinfunction "TX-_8") (pintype "passive"))
      (node (ref "U1") (pin "AK26") (pinfunction "TYPEC1_TX1M_AK26") (pintype "passive"))
      (node (ref "VD24") (pin "2") (pinfunction "IN2_2") (pintype "passive"))
    )
    (net (code "38") (name "/TYPEC1_TX1_P") (class "Default")
      (node (ref "J6") (pin "9") (pinfunction "TX+_9") (pintype "passive"))
      (node (ref "U1") (pin "AL26") (pinfunction "TYPEC1_TX1P_AL26") (pintype "passive"))
      (node (ref "VD24") (pin "1") (pinfunction "IN1_1") (pintype "passive"))
    )
    (net (code "39") (name "/VBUS_TYPEC0") (class "Default")
      (node (ref "C282") (pin "1") (pinfunction "1_1") (pintype "power_in"))
      (node (ref "C283") (pin "1") (pinfunction "1_1") (pintype "power_in"))
      (node (ref "C284") (pin "1") (pinfunction "1_1") (pintype "power_in"))
      (node (ref "C289") (pin "1") (pinfunction "1_1") (pintype "power_in"))
      (node (ref "D16") (pin "1") (pinfunction "OUT_1") (pintype "passive"))
      (node (ref "D17") (pin "2") (pinfunction "VBUS_2") (pintype "passive"))
      (node (ref "J5") (pin "A4") (pinfunction "VBUS_1_A4") (pintype "passive"))
      (node (ref "J5") (pin "A9") (pinfunction "VBUS_2_A9") (pintype "passive"))
      (node (ref "J5") (pin "B4") (pinfunction "VBUS_3_B4") (pintype "passive"))
      (node (ref "J5") (pin "B9") (pinfunction "VBUS_4_B9") (pintype "passive"))
      (node (ref "R91") (pin "2") (pinfunction "2_2") (pintype "passive"))
    )
    (net (code "40") (name "/VCC3V3_S3") (class "Default")
      (node (ref "C293") (pin "1") (pinfunction "1_1") (pintype "power_in"))
      (node (ref "C299") (pin "1") (pinfunction "1_1") (pintype "power_in"))
      (node (ref "U1") (pin "AB18") (pinfunction "TYPEC0_AVDD_3V3_AB18") (pintype "passive"))
      (node (ref "U1") (pin "AB21") (pinfunction "TYPEC1_AVDD_3V3_AB21") (pintype "passive"))
    )
    (net (code "41") (name "/VCC3V3_SYS") (class "Default")
      (node (ref "C287") (pin "1") (pinfunction "1_1") (pintype "power_in"))
      (node (ref "D17") (pin "4") (pinfunction "VDD_4") (pintype "passive"))
    )
    (net (code "42") (name "/VCC5V0_HOST_3_0") (class "Default")
      (node (ref "C304") (pin "1") (pinfunction "1_1") (pintype "power_in"))
      (node (ref "C305") (pin "1") (pinfunction "1_1") (pintype "power_in"))
      (node (ref "C306") (pin "1") (pinfunction "1_1") (pintype "power_in"))
      (node (ref "D18") (pin "1") (pinfunction "OUT_1") (pintype "passive"))
      (node (ref "J6") (pin "1") (pinfunction "VBUS_1") (pintype "passive"))
      (node (ref "VD22") (pin "2") (pinfunction "C_2") (pintype "passive"))
    )
    (net (code "43") (name "/VCC5V0_HOST_EN") (class "Default")
      (node (ref "R101") (pin "1") (pinfunction "1_1") (pintype "passive"))
    )
    (net (code "44") (name "/VCC5V0_SYS") (class "Default")
      (node (ref "C280") (pin "1") (pinfunction "1_1") (pintype "power_in"))
      (node (ref "C281") (pin "1") (pinfunction "1_1") (pintype "power_in"))
      (node (ref "C288") (pin "1") (pinfunction "1_1") (pintype "power_in"))
      (node (ref "C307") (pin "1") (pinfunction "1_1") (pintype "power_in"))
      (node (ref "C308") (pin "1") (pinfunction "1_1") (pintype "power_in"))
      (node (ref "D16") (pin "5") (pinfunction "IN_5") (pintype "passive"))
      (node (ref "D17") (pin "12") (pinfunction "VCONN_12_12") (pintype "passive"))
      (node (ref "D17") (pin "13") (pinfunction "VCONN_13_13") (pintype "passive"))
      (node (ref "D18") (pin "5") (pinfunction "IN_5") (pintype "passive"))
    )
    (net (code "45") (name "/VCC5V0_TYPEC0_EN") (class "Default")
      (node (ref "D16") (pin "4") (pinfunction "EN_4") (pintype "passive"))
    )
    (net (code "46") (name "/VCCA_0V9") (class "Default")
      (node (ref "C295") (pin "1") (pinfunction "1_1") (pintype "power_in"))
      (node (ref "C296") (pin "1") (pinfunction "1_1") (pintype "power_in"))
      (node (ref "C297") (pin "1") (pinfunction "1_1") (pintype "power_in"))
      (node (ref "U1") (pin "Y18") (pinfunction "TYPEC0_AVDD_0V9_2_Y18") (pintype "passive"))
      (node (ref "U1") (pin "Y19") (pinfunction "TYPEC0_AVDD_0V9_1_Y19") (pintype "passive"))
      (node (ref "U1") (pin "Y21") (pinfunction "TYPEC1_AVDD_0V9_1_Y21") (pintype "passive"))
      (node (ref "U1") (pin "Y22") (pinfunction "TYPEC1_AVDD_0V9_2_Y22") (pintype "passive"))
    )
    (net (code "47") (name "/VCCA_1V8") (class "Default")
      (node (ref "C294") (pin "1") (pinfunction "1_1") (pintype "power_in"))
      (node (ref "C298") (pin "1") (pinfunction "1_1") (pintype "power_in"))
      (node (ref "U1") (pin "AA18") (pinfunction "TYPEC0_AVDD_1V8_AA18") (pintype "passive"))
      (node (ref "U1") (pin "AA21") (pinfunction "TYPEC1_AVDD_1V8_AA21") (pintype "passive"))
    )
    (net (code "48") (name "Net-(D16-ISET)") (class "Default")
      (node (ref "D16") (pin "3") (pinfunction "ISET_3") (pintype "passive"))
      (node (ref "R90") (pin "1") (pinfunction "1_1") (pintype "passive"))
    )
    (net (code "49") (name "Net-(D18-EN)") (class "Default")
      (node (ref "D18") (pin "4") (pinfunction "EN_4") (pintype "passive"))
      (node (ref "R103") (pin "1") (pinfunction "1_1") (pintype "passive"))
      (node (ref "VD21") (pin "2") (pinfunction "C_2") (pintype "passive"))
    )
    (net (code "50") (name "Net-(D18-ISET)") (class "Default")
      (node (ref "D18") (pin "3") (pinfunction "ISET_3") (pintype "passive"))
      (node (ref "R102") (pin "1") (pinfunction "1_1") (pintype "passive"))
    )
    (net (code "51") (name "Net-(U1K-TYPEC0_REXT)") (class "Default")
      (node (ref "R97") (pin "1") (pinfunction "1_1") (pintype "passive"))
      (node (ref "U1") (pin "AG18") (pinfunction "TYPEC0_REXT_AG18") (pintype "passive"))
    )
    (net (code "52") (name "Net-(U1K-TYPEC0_REXT_CC)") (class "Default")
      (node (ref "R99") (pin "1") (pinfunction "1_1") (pintype "passive"))
      (node (ref "U1") (pin "AG20") (pinfunction "TYPEC0_REXT_CC_AG20") (pintype "passive"))
    )
    (net (code "53") (name "Net-(U1K-TYPEC1_REXT)") (class "Default")
      (node (ref "R98") (pin "2") (pinfunction "2_2") (pintype "passive"))
      (node (ref "U1") (pin "AE21") (pinfunction "TYPEC1_REXT_AE21") (pintype "passive"))
    )
    (net (code "54") (name "Net-(U1K-TYPEC1_REXT_CC)") (class "Default")
      (node (ref "R100") (pin "2") (pinfunction "2_2") (pintype "passive"))
      (node (ref "U1") (pin "AG21") (pinfunction "TYPEC1_REXT_CC_AG21") (pintype "passive"))
    )
    (net (code "55") (name "Net-(VD21-A)") (class "Default")
      (node (ref "R101") (pin "2") (pinfunction "2_2") (pintype "passive"))
      (node (ref "VD21") (pin "1") (pinfunction "A_1") (pintype "passive"))
    )
    (net (code "56") (name "unconnected-(D17-NC1-Pad3)") (class "Default")
      (node (ref "D17") (pin "3") (pinfunction "NC1_3") (pintype "passive"))
    )
    (net (code "57") (name "unconnected-(D17-NC2-Pad8)") (class "Default")
      (node (ref "D17") (pin "8") (pinfunction "NC2_8") (pintype "passive"))
    )
    (net (code "58") (name "unconnected-(J5-HOLE_1-PadH1)") (class "Default")
      (node (ref "J5") (pin "H1") (pinfunction "HOLE_1_H1") (pintype "passive"))
    )
    (net (code "59") (name "unconnected-(J5-HOLE_2-PadH2)") (class "Default")
      (node (ref "J5") (pin "H2") (pinfunction "HOLE_2_H2") (pintype "passive"))
    )
    (net (code "60") (name "unconnected-(U1K-TYPEC0_CC1-PadAH18)") (class "Default")
      (node (ref "U1") (pin "AH18") (pinfunction "TYPEC0_CC1_AH18") (pintype "passive"))
    )
    (net (code "61") (name "unconnected-(U1K-TYPEC0_CC2-PadAH20)") (class "Default")
      (node (ref "U1") (pin "AH20") (pinfunction "TYPEC0_CC2_AH20") (pintype "passive"))
    )
    (net (code "62") (name "unconnected-(U1K-TYPEC1_AUXM-PadAL29)") (class "Default")
      (node (ref "U1") (pin "AL29") (pinfunction "TYPEC1_AUXM_AL29") (pintype "passive"))
    )
    (net (code "63") (name "unconnected-(U1K-TYPEC1_AUXM_PU_PD-PadAF25)") (class "Default")
      (node (ref "U1") (pin "AF25") (pinfunction "TYPEC1_AUXM_PU_PD_AF25") (pintype "passive"))
    )
    (net (code "64") (name "unconnected-(U1K-TYPEC1_AUXP-PadAK29)") (class "Default")
      (node (ref "U1") (pin "AK29") (pinfunction "TYPEC1_AUXP_AK29") (pintype "passive"))
    )
    (net (code "65") (name "unconnected-(U1K-TYPEC1_AUXP_PD_PU-PadAE24)") (class "Default")
      (node (ref "U1") (pin "AE24") (pinfunction "TYPEC1_AUXP_PD_PU_AE24") (pintype "passive"))
    )
    (net (code "66") (name "unconnected-(U1K-TYPEC1_CC1-PadAH21)") (class "Default")
      (node (ref "U1") (pin "AH21") (pinfunction "TYPEC1_CC1_AH21") (pintype "passive"))
    )
    (net (code "67") (name "unconnected-(U1K-TYPEC1_CC2-PadAF21)") (class "Default")
      (node (ref "U1") (pin "AF21") (pinfunction "TYPEC1_CC2_AF21") (pintype "passive"))
    )
    (net (code "68") (name "unconnected-(U1K-TYPEC1_ID-PadAE26)") (class "Default")
      (node (ref "U1") (pin "AE26") (pinfunction "TYPEC1_ID_AE26") (pintype "passive"))
    )
    (net (code "69") (name "unconnected-(U1K-TYPEC1_RCLKM-PadAD20)") (class "Default")
      (node (ref "U1") (pin "AD20") (pinfunction "TYPEC1_RCLKM_AD20") (pintype "passive"))
    )
    (net (code "70") (name "unconnected-(U1K-TYPEC1_RCLKP-PadAE20)") (class "Default")
      (node (ref "U1") (pin "AE20") (pinfunction "TYPEC1_RCLKP_AE20") (pintype "passive"))
    )
    (net (code "71") (name "unconnected-(U1K-TYPEC1_RX2M-PadAL27)") (class "Default")
      (node (ref "U1") (pin "AL27") (pinfunction "TYPEC1_RX2M_AL27") (pintype "passive"))
    )
    (net (code "72") (name "unconnected-(U1K-TYPEC1_RX2P-PadAK27)") (class "Default")
      (node (ref "U1") (pin "AK27") (pinfunction "TYPEC1_RX2P_AK27") (pintype "passive"))
    )
    (net (code "73") (name "unconnected-(U1K-TYPEC1_TX2M-PadAK28)") (class "Default")
      (node (ref "U1") (pin "AK28") (pinfunction "TYPEC1_TX2M_AK28") (pintype "passive"))
    )
    (net (code "74") (name "unconnected-(U1K-TYPEC1_TX2P-PadAL28)") (class "Default")
      (node (ref "U1") (pin "AL28") (pinfunction "TYPEC1_TX2P_AL28") (pintype "passive"))
    )
    (net (code "75") (name "unconnected-(U1K-TYPEC1_U2VBUSDET-PadAK31)") (class "Default")
      (node (ref "U1") (pin "AK31") (pinfunction "TYPEC1_U2VBUSDET_AK31") (pintype "passive"))
    )
    (net (code "76") (name "unconnected-(VD16-IN3-Pad4)") (class "Default")
      (node (ref "VD16") (pin "4") (pinfunction "IN3_4") (pintype "passive"))
    )
    (net (code "77") (name "unconnected-(VD16-IN4-Pad5)") (class "Default")
      (node (ref "VD16") (pin "5") (pinfunction "IN4_5") (pintype "passive"))
    )
    (net (code "78") (name "unconnected-(VD23-IN3-Pad4)") (class "Default")
      (node (ref "VD23") (pin "4") (pinfunction "IN3_4") (pintype "passive"))
    )
    (net (code "79") (name "unconnected-(VD23-IN4-Pad5)") (class "Default")
      (node (ref "VD23") (pin "5") (pinfunction "IN4_5") (pintype "passive"))
    )
  )
)
